# ENET.net
KiCad netlist of a schematic drawn in Altium Designer
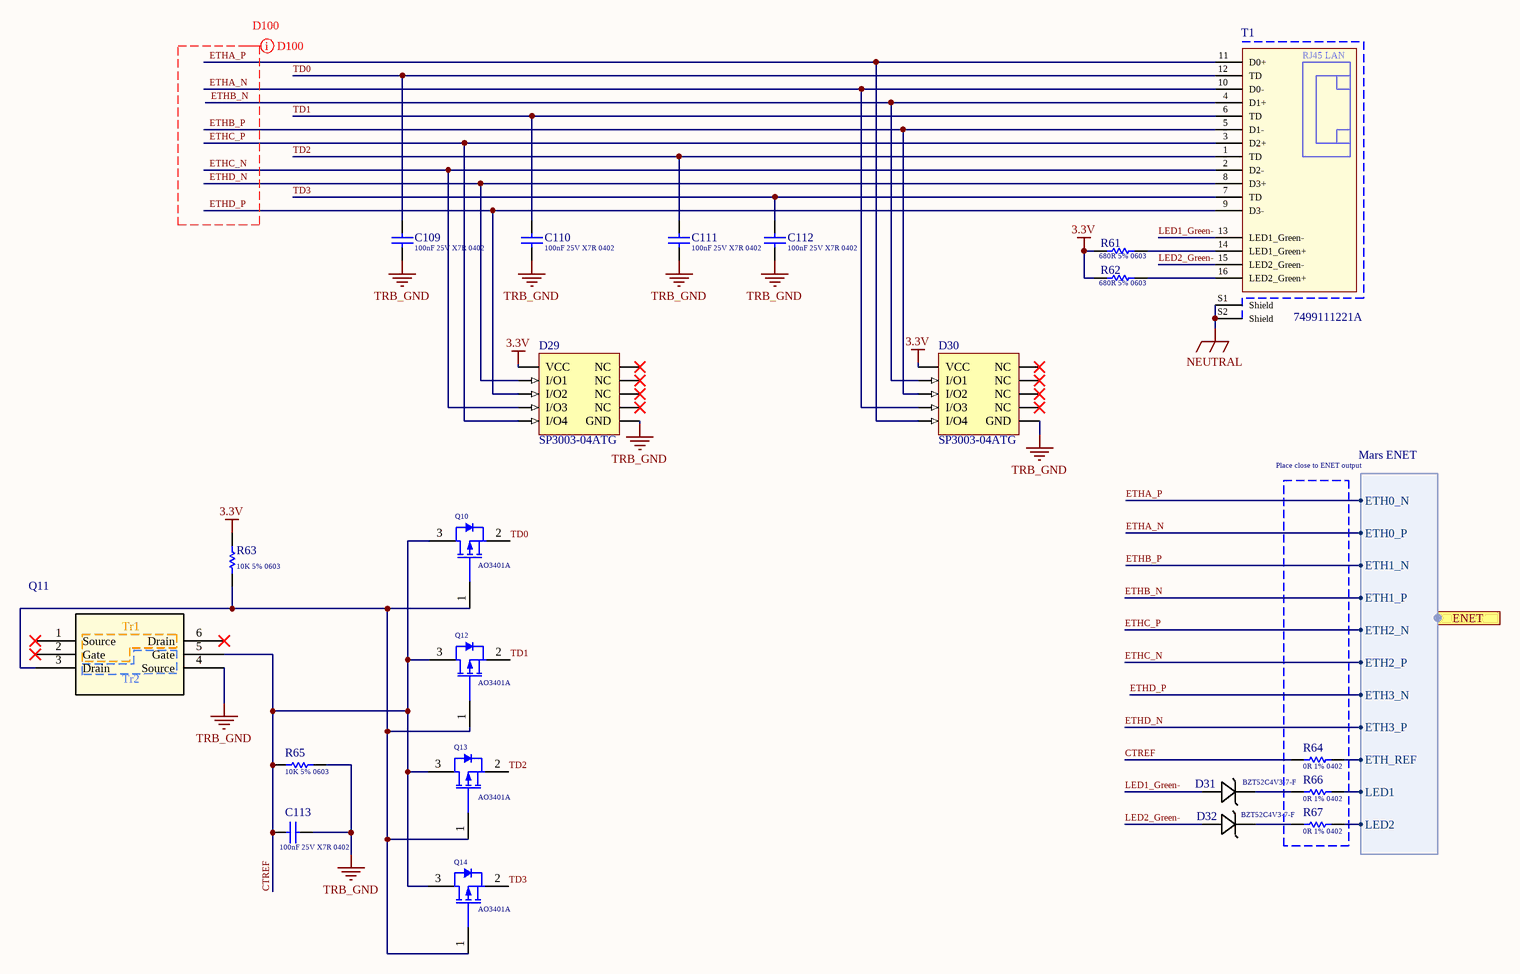
[diagram p0: ENET.SchDoc]

(export (version "E")
  (design (tool "Eeschema 10.0.6"))
  (components
    (comp (ref "C109")
      (value "Cap_Taiyo_Yuden_TMK105B7104KV-FR_100nF")
      (footprint "Cap_Taiyo_Yuden_TMK105B7104KV-FR_100nF")
      (description "CAP CER 100nF 25V X7R 0402")
      (fields (field (name "CAPACITANCE") "100nF 25V X7R 0402"))
      (libsource (lib "Cap_Taiyo_Yuden_TMK105B7104KV-FR_100nF") (part "Cap_Taiyo_Yuden_TMK105B7104KV-FR_100nF"))
    )
    (comp (ref "C110")
      (value "Cap_Taiyo_Yuden_TMK105B7104KV-FR_100nF")
      (footprint "Cap_Taiyo_Yuden_TMK105B7104KV-FR_100nF")
      (description "CAP CER 100nF 25V X7R 0402")
      (fields (field (name "CAPACITANCE") "100nF 25V X7R 0402"))
      (libsource (lib "Cap_Taiyo_Yuden_TMK105B7104KV-FR_100nF") (part "Cap_Taiyo_Yuden_TMK105B7104KV-FR_100nF"))
    )
    (comp (ref "C111")
      (value "Cap_Taiyo_Yuden_TMK105B7104KV-FR_100nF")
      (footprint "Cap_Taiyo_Yuden_TMK105B7104KV-FR_100nF")
      (description "CAP CER 100nF 25V X7R 0402")
      (fields (field (name "CAPACITANCE") "100nF 25V X7R 0402"))
      (libsource (lib "Cap_Taiyo_Yuden_TMK105B7104KV-FR_100nF") (part "Cap_Taiyo_Yuden_TMK105B7104KV-FR_100nF"))
    )
    (comp (ref "C112")
      (value "Cap_Taiyo_Yuden_TMK105B7104KV-FR_100nF")
      (footprint "Cap_Taiyo_Yuden_TMK105B7104KV-FR_100nF")
      (description "CAP CER 100nF 25V X7R 0402")
      (fields (field (name "CAPACITANCE") "100nF 25V X7R 0402"))
      (libsource (lib "Cap_Taiyo_Yuden_TMK105B7104KV-FR_100nF") (part "Cap_Taiyo_Yuden_TMK105B7104KV-FR_100nF"))
    )
    (comp (ref "C113")
      (value "Cap_Taiyo_Yuden_TMK105B7104KV-FR_100nF")
      (footprint "Cap_Taiyo_Yuden_TMK105B7104KV-FR_100nF")
      (description "CAP CER 100nF 25V X7R 0402")
      (fields (field (name "CAPACITANCE") "100nF 25V X7R 0402"))
      (libsource (lib "Cap_Taiyo_Yuden_TMK105B7104KV-FR_100nF") (part "Cap_Taiyo_Yuden_TMK105B7104KV-FR_100nF"))
    )
    (comp (ref "D29")
      (value "Diode_SP3003-04ATG_LVDS_ESD")
      (footprint "Diode_SP3003-04ATG_LVDS_ESD")
      (description "ESD Suppressors / TVS Diodes 4 Ch 8kV 0.65pF SPA")
      (fields (field (name "SERIES") "SP3003-04ATG"))
      (libsource (lib "Diode_SP3003-04ATG_LVDS_ESD") (part "Diode_SP3003-04ATG_LVDS_ESD"))
    )
    (comp (ref "D30")
      (value "Diode_SP3003-04ATG_LVDS_ESD")
      (footprint "Diode_SP3003-04ATG_LVDS_ESD")
      (description "ESD Suppressors / TVS Diodes 4 Ch 8kV 0.65pF SPA")
      (fields (field (name "SERIES") "SP3003-04ATG"))
      (libsource (lib "Diode_SP3003-04ATG_LVDS_ESD") (part "Diode_SP3003-04ATG_LVDS_ESD"))
    )
    (comp (ref "D31")
      (value "BZT52C4V3-7-F")
      (footprint "SOD123")
      (description "Zener Diodes 500mW 4.3V Zener AEC-Q101 Qualified")
      (fields (field (name "SERIES") "BZT52C4V3-7-F"))
      (libsource (lib "4v3_zener_BZT52C4V3-7-F") (part "BZT52C4V3-7-F"))
    )
    (comp (ref "D32")
      (value "BZT52C4V3-7-F")
      (footprint "SOD123")
      (description "Zener Diodes 500mW 4.3V Zener AEC-Q101 Qualified")
      (fields (field (name "SERIES") "BZT52C4V3-7-F"))
      (libsource (lib "4v3_zener_BZT52C4V3-7-F") (part "BZT52C4V3-7-F"))
    )
    (comp (ref "Q10")
      (value "Mos_Alpha&Omega_AO3401A_4A")
      (footprint "Mos_Alpha&Omega_AO3401A_4A")
      (description "P-Channel 30V 4A (Ta) 1.4W (Ta) Surface Mount SOT-23-3L")
      (fields (field (name "SERIES") "AO3401A"))
      (libsource (lib "Mos_Alpha&Omega_AO3401A_4A") (part "Mos_Alpha&Omega_AO3401A_4A"))
    )
    (comp (ref "Q11")
      (value "EM6K6T2R")
      (footprint "TRANS_EM6_ROM")
      (description "MOSFET Small Signal Dual N-CH 20V .3A .15W")
      (libsource (lib "Trans_NFET_ROHM_EM6K6T2R") (part "EM6K6T2R"))
    )
    (comp (ref "Q12")
      (value "Mos_Alpha&Omega_AO3401A_4A")
      (footprint "Mos_Alpha&Omega_AO3401A_4A")
      (description "P-Channel 30V 4A (Ta) 1.4W (Ta) Surface Mount SOT-23-3L")
      (fields (field (name "SERIES") "AO3401A"))
      (libsource (lib "Mos_Alpha&Omega_AO3401A_4A") (part "Mos_Alpha&Omega_AO3401A_4A"))
    )
    (comp (ref "Q13")
      (value "Mos_Alpha&Omega_AO3401A_4A")
      (footprint "Mos_Alpha&Omega_AO3401A_4A")
      (description "P-Channel 30V 4A (Ta) 1.4W (Ta) Surface Mount SOT-23-3L")
      (fields (field (name "SERIES") "AO3401A"))
      (libsource (lib "Mos_Alpha&Omega_AO3401A_4A") (part "Mos_Alpha&Omega_AO3401A_4A"))
    )
    (comp (ref "Q14")
      (value "Mos_Alpha&Omega_AO3401A_4A")
      (footprint "Mos_Alpha&Omega_AO3401A_4A")
      (description "P-Channel 30V 4A (Ta) 1.4W (Ta) Surface Mount SOT-23-3L")
      (fields (field (name "SERIES") "AO3401A"))
      (libsource (lib "Mos_Alpha&Omega_AO3401A_4A") (part "Mos_Alpha&Omega_AO3401A_4A"))
    )
    (comp (ref "R61")
      (value "680R 5% 0603")
      (footprint "RESC0603(1608)_L")
      (description "680R 0.1W 5% 0603 (1608 Metric)  SMD")
      (fields (field (name "TOLERANCE") "5 %") (field (name "POWER") "0.1 W"))
      (libsource (lib "Altium Content Vault") (part "RES"))
    )
    (comp (ref "R62")
      (value "680R 5% 0603")
      (footprint "RESC0603(1608)_L")
      (description "680R 0.1W 5% 0603 (1608 Metric)  SMD")
      (fields (field (name "TOLERANCE") "5 %") (field (name "POWER") "0.1 W"))
      (libsource (lib "Altium Content Vault") (part "RES"))
    )
    (comp (ref "R63")
      (value "10K 5% 0603")
      (footprint "RESC0603(1608)_L")
      (description "10K 0.1W 5% 0603 (1608 Metric)  SMD")
      (fields (field (name "TOLERANCE") "5 %") (field (name "POWER") "0.1 W"))
      (libsource (lib "Altium Content Vault") (part "RES"))
    )
    (comp (ref "R64")
      (value "Res_Vishay_CRCW04020000Z0EDC_0_Ohm")
      (footprint "Res_Vishay_CRCW04020000Z0EDC_0_Ohm")
      (description "0R 0.062W 1% 0402 (1005 Metric)  SMD")
      (fields (field (name "RESISTANCE") "0R 1% 0402"))
      (libsource (lib "Res_Vishay_CRCW04020000Z0EDC_0_Ohm") (part "Res_Vishay_CRCW04020000Z0EDC_0_Ohm"))
    )
    (comp (ref "R65")
      (value "10K 5% 0603")
      (footprint "RESC0603(1608)_L")
      (description "10K 0.1W 5% 0603 (1608 Metric)  SMD")
      (fields (field (name "TOLERANCE") "5 %") (field (name "POWER") "0.1 W"))
      (libsource (lib "Altium Content Vault") (part "RES"))
    )
    (comp (ref "R66")
      (value "Res_Vishay_CRCW04020000Z0EDC_0_Ohm")
      (footprint "Res_Vishay_CRCW04020000Z0EDC_0_Ohm")
      (description "0R 0.062W 1% 0402 (1005 Metric)  SMD")
      (fields (field (name "RESISTANCE") "0R 1% 0402"))
      (libsource (lib "Res_Vishay_CRCW04020000Z0EDC_0_Ohm") (part "Res_Vishay_CRCW04020000Z0EDC_0_Ohm"))
    )
    (comp (ref "R67")
      (value "Res_Vishay_CRCW04020000Z0EDC_0_Ohm")
      (footprint "Res_Vishay_CRCW04020000Z0EDC_0_Ohm")
      (description "0R 0.062W 1% 0402 (1005 Metric)  SMD")
      (fields (field (name "RESISTANCE") "0R 1% 0402"))
      (libsource (lib "Res_Vishay_CRCW04020000Z0EDC_0_Ohm") (part "Res_Vishay_CRCW04020000Z0EDC_0_Ohm"))
    )
    (comp (ref "T1")
      (value "7499111221A")
      (footprint "7499111221A")
      (description "WE-RJ45 LAN Transformer, 10/100/1000 Base-T, THT, Port 1x1, Tab Up")
      (fields (field (name "PUBLISHER") "Wurth Elektronik"))
      (libsource (lib "Wurth-RJ45-7499111221A") (part "7499111221A"))
    )
  )
  (nets
    (net (code "3") (name "/CTREF") (class "Default")
      (node (ref "C113") (pin "2") (pinfunction "2_2") (pintype "passive"))
      (node (ref "Q10") (pin "3") (pinfunction "D_3") (pintype "passive"))
      (node (ref "Q11") (pin "5") (pinfunction "Gate_5") (pintype "passive"))
      (node (ref "Q12") (pin "3") (pinfunction "D_3") (pintype "passive"))
      (node (ref "Q13") (pin "3") (pinfunction "D_3") (pintype "passive"))
      (node (ref "Q14") (pin "3") (pinfunction "D_3") (pintype "passive"))
      (node (ref "R64") (pin "1") (pinfunction "1_1") (pintype "passive"))
      (node (ref "R65") (pin "2") (pinfunction "2_2") (pintype "passive"))
    )
    (net (code "4") (name "/ETHA_N") (class "Default")
      (node (ref "D30") (pin "4") (pinfunction "I/O3_4") (pintype "input"))
      (node (ref "T1") (pin "10") (pinfunction "D0-_10") (pintype "passive"))
    )
    (net (code "5") (name "/ETHA_P") (class "Default")
      (node (ref "D30") (pin "5") (pinfunction "I/O4_5") (pintype "input"))
      (node (ref "T1") (pin "11") (pinfunction "D0+_11") (pintype "passive"))
    )
    (net (code "6") (name "/ETHB_N") (class "Default")
      (node (ref "D30") (pin "1") (pinfunction "I/O1_1") (pintype "input"))
      (node (ref "T1") (pin "4") (pinfunction "D1+_4") (pintype "passive"))
    )
    (net (code "7") (name "/ETHB_P") (class "Default")
      (node (ref "D30") (pin "2") (pinfunction "I/O2_2") (pintype "input"))
      (node (ref "T1") (pin "5") (pinfunction "D1-_5") (pintype "passive"))
    )
    (net (code "8") (name "/ETHC_N") (class "Default")
      (node (ref "D29") (pin "4") (pinfunction "I/O3_4") (pintype "input"))
      (node (ref "T1") (pin "2") (pinfunction "D2-_2") (pintype "passive"))
    )
    (net (code "9") (name "/ETHC_P") (class "Default")
      (node (ref "D29") (pin "5") (pinfunction "I/O4_5") (pintype "input"))
      (node (ref "T1") (pin "3") (pinfunction "D2+_3") (pintype "passive"))
    )
    (net (code "10") (name "/ETHD_N") (class "Default")
      (node (ref "D29") (pin "1") (pinfunction "I/O1_1") (pintype "input"))
      (node (ref "T1") (pin "8") (pinfunction "D3+_8") (pintype "passive"))
    )
    (net (code "11") (name "/ETHD_P") (class "Default")
      (node (ref "D29") (pin "2") (pinfunction "I/O2_2") (pintype "input"))
      (node (ref "T1") (pin "9") (pinfunction "D3-_9") (pintype "passive"))
    )
    (net (code "12") (name "/ETH_REF") (class "Default")
      (node (ref "R64") (pin "2") (pinfunction "2_2") (pintype "passive"))
    )
    (net (code "13") (name "/LED1") (class "Default")
      (node (ref "R66") (pin "2") (pinfunction "2_2") (pintype "passive"))
    )
    (net (code "14") (name "/LED1_Green-") (class "Default")
      (node (ref "D31") (pin "2") (pinfunction "2_2") (pintype "passive"))
      (node (ref "T1") (pin "13") (pinfunction "LED1_Green-_13") (pintype "passive"))
    )
    (net (code "15") (name "/LED2") (class "Default")
      (node (ref "R67") (pin "2") (pinfunction "2_2") (pintype "passive"))
    )
    (net (code "16") (name "/LED2_Green-") (class "Default")
      (node (ref "D32") (pin "2") (pinfunction "2_2") (pintype "passive"))
      (node (ref "T1") (pin "15") (pinfunction "LED2_Green-_15") (pintype "passive"))
    )
    (net (code "17") (name "/TD0") (class "Default")
      (node (ref "C109") (pin "2") (pinfunction "2_2") (pintype "passive"))
      (node (ref "Q10") (pin "2") (pinfunction "S_2") (pintype "passive"))
      (node (ref "T1") (pin "12") (pinfunction "TD_12") (pintype "passive"))
    )
    (net (code "18") (name "/TD1") (class "Default")
      (node (ref "C110") (pin "2") (pinfunction "2_2") (pintype "passive"))
      (node (ref "Q12") (pin "2") (pinfunction "S_2") (pintype "passive"))
      (node (ref "T1") (pin "6") (pinfunction "TD_6") (pintype "passive"))
    )
    (net (code "19") (name "/TD2") (class "Default")
      (node (ref "C111") (pin "2") (pinfunction "2_2") (pintype "passive"))
      (node (ref "Q13") (pin "2") (pinfunction "S_2") (pintype "passive"))
      (node (ref "T1") (pin "1") (pinfunction "TD_1") (pintype "passive"))
    )
    (net (code "20") (name "/TD3") (class "Default")
      (node (ref "C112") (pin "2") (pinfunction "2_2") (pintype "passive"))
      (node (ref "Q14") (pin "2") (pinfunction "S_2") (pintype "passive"))
      (node (ref "T1") (pin "7") (pinfunction "TD_7") (pintype "passive"))
    )
    (net (code "22") (name "3.3V") (class "Default")
      (node (ref "D29") (pin "3") (pinfunction "VCC_3") (pintype "passive"))
      (node (ref "D30") (pin "3") (pinfunction "VCC_3") (pintype "passive"))
      (node (ref "R61") (pin "1") (pinfunction "1_1") (pintype "passive"))
      (node (ref "R62") (pin "1") (pinfunction "1_1") (pintype "passive"))
      (node (ref "R63") (pin "2") (pinfunction "2_2") (pintype "passive"))
    )
    (net (code "23") (name "NEUTRAL") (class "Default")
      (node (ref "T1") (pin "S1") (pinfunction "Shield_S1") (pintype "passive"))
      (node (ref "T1") (pin "S2") (pinfunction "Shield_S2") (pintype "passive"))
    )
    (net (code "24") (name "Net-(D31-Pad1)") (class "Default")
      (node (ref "D31") (pin "1") (pinfunction "1_1") (pintype "passive"))
      (node (ref "R66") (pin "1") (pinfunction "1_1") (pintype "passive"))
    )
    (net (code "25") (name "Net-(D32-Pad1)") (class "Default")
      (node (ref "D32") (pin "1") (pinfunction "1_1") (pintype "passive"))
      (node (ref "R67") (pin "1") (pinfunction "1_1") (pintype "passive"))
    )
    (net (code "26") (name "Net-(Q10-G)") (class "Default")
      (node (ref "Q10") (pin "1") (pinfunction "G_1") (pintype "passive"))
      (node (ref "Q11") (pin "3") (pinfunction "Drain_3") (pintype "passive"))
      (node (ref "Q12") (pin "1") (pinfunction "G_1") (pintype "passive"))
      (node (ref "Q13") (pin "1") (pinfunction "G_1") (pintype "passive"))
      (node (ref "Q14") (pin "1") (pinfunction "G_1") (pintype "passive"))
      (node (ref "R63") (pin "1") (pinfunction "1_1") (pintype "passive"))
    )
    (net (code "27") (name "Net-(T1-LED1_Green+)") (class "Default")
      (node (ref "R61") (pin "2") (pinfunction "2_2") (pintype "passive"))
      (node (ref "T1") (pin "14") (pinfunction "LED1_Green+_14") (pintype "passive"))
    )
    (net (code "28") (name "Net-(T1-LED2_Green+)") (class "Default")
      (node (ref "R62") (pin "2") (pinfunction "2_2") (pintype "passive"))
      (node (ref "T1") (pin "16") (pinfunction "LED2_Green+_16") (pintype "passive"))
    )
    (net (code "29") (name "TRB_GND") (class "Default")
      (node (ref "C109") (pin "1") (pinfunction "1_1") (pintype "passive"))
      (node (ref "C110") (pin "1") (pinfunction "1_1") (pintype "passive"))
      (node (ref "C111") (pin "1") (pinfunction "1_1") (pintype "passive"))
      (node (ref "C112") (pin "1") (pinfunction "1_1") (pintype "passive"))
      (node (ref "C113") (pin "1") (pinfunction "1_1") (pintype "passive"))
      (node (ref "D29") (pin "8") (pinfunction "GND_8") (pintype "power_in"))
      (node (ref "D30") (pin "8") (pinfunction "GND_8") (pintype "power_in"))
      (node (ref "Q11") (pin "4") (pinfunction "Source_4") (pintype "passive"))
      (node (ref "R65") (pin "1") (pinfunction "1_1") (pintype "passive"))
    )
    (net (code "30") (name "unconnected-(D29-NC-Pad6)") (class "Default")
      (node (ref "D29") (pin "6") (pinfunction "NC_6") (pintype "tri_state+no_connect"))
    )
    (net (code "31") (name "unconnected-(D29-NC-Pad7)") (class "Default")
      (node (ref "D29") (pin "7") (pinfunction "NC_7") (pintype "tri_state+no_connect"))
    )
    (net (code "32") (name "unconnected-(D29-NC-Pad9)") (class "Default")
      (node (ref "D29") (pin "9") (pinfunction "NC_9") (pintype "tri_state+no_connect"))
    )
    (net (code "33") (name "unconnected-(D29-NC-Pad10)") (class "Default")
      (node (ref "D29") (pin "10") (pinfunction "NC_10") (pintype "tri_state+no_connect"))
    )
    (net (code "34") (name "unconnected-(D30-NC-Pad6)") (class "Default")
      (node (ref "D30") (pin "6") (pinfunction "NC_6") (pintype "tri_state+no_connect"))
    )
    (net (code "35") (name "unconnected-(D30-NC-Pad7)") (class "Default")
      (node (ref "D30") (pin "7") (pinfunction "NC_7") (pintype "tri_state+no_connect"))
    )
    (net (code "36") (name "unconnected-(D30-NC-Pad9)") (class "Default")
      (node (ref "D30") (pin "9") (pinfunction "NC_9") (pintype "tri_state+no_connect"))
    )
    (net (code "37") (name "unconnected-(D30-NC-Pad10)") (class "Default")
      (node (ref "D30") (pin "10") (pinfunction "NC_10") (pintype "tri_state+no_connect"))
    )
    (net (code "38") (name "unconnected-(Q11-Drain-Pad6)") (class "Default")
      (node (ref "Q11") (pin "6") (pinfunction "Drain_6") (pintype "passive+no_connect"))
    )
    (net (code "39") (name "unconnected-(Q11-Gate-Pad2)") (class "Default")
      (node (ref "Q11") (pin "2") (pinfunction "Gate_2") (pintype "passive+no_connect"))
    )
    (net (code "40") (name "unconnected-(Q11-Source-Pad1)") (class "Default")
      (node (ref "Q11") (pin "1") (pinfunction "Source_1") (pintype "passive+no_connect"))
    )
  )
)
